# qtpy_midibff_disp.net
KiCad netlist of a schematic drawn in EAGLE
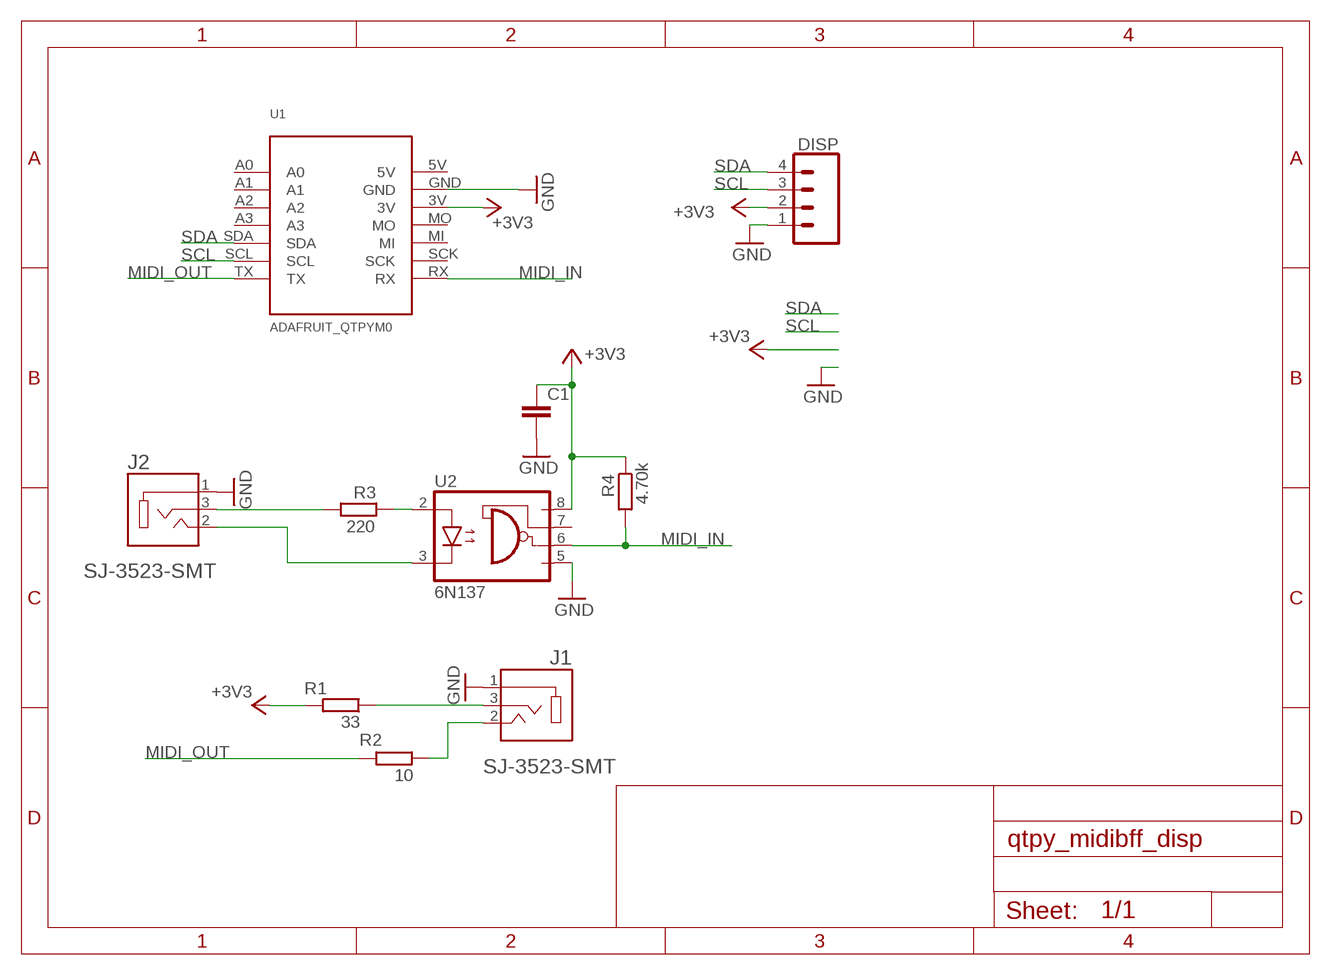
[diagram p0: schematic, sheet 1]

(export (version "E")
  (design (tool "Eeschema 10.0.6"))
  (components
    (comp (ref "C1")
      (value "C-EU025-025X050")
      (footprint "eagle-import:C025-025X050")
      (libsource (lib "eagle-import") (part "C-EU025-025X050"))
    )
    (comp (ref "DISP")
      (value "CONN_04")
      (footprint "eagle-import:1X04")
      (libsource (lib "eagle-import") (part "CONN_04"))
    )
    (comp (ref "J1")
      (value "SJ-3523-SMT")
      (footprint "eagle-import:CUI_SJ-3523-SMT")
      (fields
        (field (name "DIGI-KEY_PART_NUMBER") "CP-3523SJCT-ND")
        (field (name "MF") "CUI Devices")
        (field (name "MP") "SJ-3523-SMT-TR")
      )
      (libsource (lib "eagle-import") (part "SJ-3523-SMT"))
    )
    (comp (ref "J2")
      (value "SJ-3523-SMT")
      (footprint "eagle-import:CUI_SJ-3523-SMT")
      (fields
        (field (name "DIGI-KEY_PART_NUMBER") "CP-3523SJCT-ND")
        (field (name "MF") "CUI Devices")
        (field (name "MP") "SJ-3523-SMT-TR")
      )
      (libsource (lib "eagle-import") (part "SJ-3523-SMT"))
    )
    (comp (ref "R1")
      (value "33")
      (footprint "eagle-import:0204_7")
      (libsource (lib "eagle-import") (part "R-EU_0204/7"))
    )
    (comp (ref "R2")
      (value "10")
      (footprint "eagle-import:0204_7")
      (libsource (lib "eagle-import") (part "R-EU_0204/7"))
    )
    (comp (ref "R3")
      (value "220")
      (footprint "eagle-import:0204_7")
      (libsource (lib "eagle-import") (part "R-EU_0204/7"))
    )
    (comp (ref "R4")
      (value "4.70k")
      (footprint "eagle-import:0204_7")
      (libsource (lib "eagle-import") (part "R-EU_0204/7"))
    )
    (comp (ref "U1")
      (value "ADAFRUIT_QTPYM0")
      (footprint "eagle-import:ADAFRUIT_QTPY_M0")
      (libsource (lib "eagle-import") (part "ADAFRUIT_QTPYM0"))
    )
    (comp (ref "U2")
      (value "6N137")
      (footprint "eagle-import:DIL08")
      (libsource (lib "eagle-import") (part "6N137"))
    )
  )
  (nets
    (net (code "1") (name "+3V3") (class "Default")
      (node (ref "C1") (pin "1") (pinfunction "1_1") (pintype "passive"))
      (node (ref "DISP") (pin "2") (pinfunction "2_2") (pintype "passive"))
      (node (ref "R1") (pin "2") (pinfunction "2_2") (pintype "passive"))
      (node (ref "R4") (pin "1") (pinfunction "1_1") (pintype "passive"))
      (node (ref "U1") (pin "3V") (pinfunction "3V_3V") (pintype "bidirectional"))
      (node (ref "U2") (pin "8") (pinfunction "VCC_8") (pintype "passive"))
    )
    (net (code "2") (name "/MIDI_IN") (class "Default")
      (node (ref "R4") (pin "2") (pinfunction "2_2") (pintype "passive"))
      (node (ref "U1") (pin "RX") (pinfunction "RX_RX") (pintype "bidirectional"))
      (node (ref "U2") (pin "6") (pinfunction "VO_6") (pintype "passive"))
    )
    (net (code "3") (name "/MIDI_OUT") (class "Default")
      (node (ref "R2") (pin "2") (pinfunction "2_2") (pintype "passive"))
      (node (ref "U1") (pin "TX") (pinfunction "TX_TX") (pintype "bidirectional"))
    )
    (net (code "4") (name "/SCL") (class "Default")
      (node (ref "DISP") (pin "3") (pinfunction "3_3") (pintype "passive"))
      (node (ref "U1") (pin "SCL") (pinfunction "SCL_SCL") (pintype "bidirectional"))
    )
    (net (code "5") (name "/SDA") (class "Default")
      (node (ref "DISP") (pin "4") (pinfunction "4_4") (pintype "passive"))
      (node (ref "U1") (pin "SDA") (pinfunction "SDA_SDA") (pintype "bidirectional"))
    )
    (net (code "6") (name "GND") (class "Default")
      (node (ref "C1") (pin "2") (pinfunction "2_2") (pintype "passive"))
      (node (ref "DISP") (pin "1") (pinfunction "1_1") (pintype "passive"))
      (node (ref "J1") (pin "1") (pinfunction "1_1") (pintype "passive"))
      (node (ref "J2") (pin "1") (pinfunction "1_1") (pintype "passive"))
      (node (ref "U1") (pin "GND") (pinfunction "GND_GND") (pintype "bidirectional"))
      (node (ref "U2") (pin "5") (pinfunction "GND_5") (pintype "passive"))
    )
    (net (code "7") (name "Net-(J1-Pad2)") (class "Default")
      (node (ref "J1") (pin "2") (pinfunction "2_2") (pintype "passive"))
      (node (ref "R2") (pin "1") (pinfunction "1_1") (pintype "passive"))
    )
    (net (code "8") (name "Net-(J1-Pad3)") (class "Default")
      (node (ref "J1") (pin "3") (pinfunction "3_3") (pintype "passive"))
      (node (ref "R1") (pin "1") (pinfunction "1_1") (pintype "passive"))
    )
    (net (code "9") (name "Net-(J2-Pad3)") (class "Default")
      (node (ref "J2") (pin "3") (pinfunction "3_3") (pintype "passive"))
      (node (ref "R3") (pin "2") (pinfunction "2_2") (pintype "passive"))
    )
    (net (code "10") (name "Net-(U2-A)") (class "Default")
      (node (ref "R3") (pin "1") (pinfunction "1_1") (pintype "passive"))
      (node (ref "U2") (pin "2") (pinfunction "A_2") (pintype "passive"))
    )
    (net (code "11") (name "Net-(U2-C)") (class "Default")
      (node (ref "J2") (pin "2") (pinfunction "2_2") (pintype "passive"))
      (node (ref "U2") (pin "3") (pinfunction "C_3") (pintype "passive"))
    )
    (net (code "12") (name "unconnected-(U1-Pad5V)") (class "Default")
      (node (ref "U1") (pin "5V") (pinfunction "5V_5V") (pintype "bidirectional"))
    )
    (net (code "13") (name "unconnected-(U1-PadA0)") (class "Default")
      (node (ref "U1") (pin "A0") (pinfunction "A0_A0") (pintype "bidirectional"))
    )
    (net (code "14") (name "unconnected-(U1-PadA1)") (class "Default")
      (node (ref "U1") (pin "A1") (pinfunction "A1_A1") (pintype "bidirectional"))
    )
    (net (code "15") (name "unconnected-(U1-PadA2)") (class "Default")
      (node (ref "U1") (pin "A2") (pinfunction "A2_A2") (pintype "bidirectional"))
    )
    (net (code "16") (name "unconnected-(U1-PadA3)") (class "Default")
      (node (ref "U1") (pin "A3") (pinfunction "A3_A3") (pintype "bidirectional"))
    )
    (net (code "17") (name "unconnected-(U1-PadMI)") (class "Default")
      (node (ref "U1") (pin "MI") (pinfunction "MI_MI") (pintype "bidirectional"))
    )
    (net (code "18") (name "unconnected-(U1-PadMO)") (class "Default")
      (node (ref "U1") (pin "MO") (pinfunction "MO_MO") (pintype "bidirectional"))
    )
    (net (code "19") (name "unconnected-(U1-PadSCK)") (class "Default")
      (node (ref "U1") (pin "SCK") (pinfunction "SCK_SCK") (pintype "bidirectional"))
    )
    (net (code "20") (name "unconnected-(U2-VE-Pad7)") (class "Default")
      (node (ref "U2") (pin "7") (pinfunction "VE_7") (pintype "passive"))
    )
  )
)
